# RAM.net
KiCad netlist of a schematic drawn in EasyEDA Pro
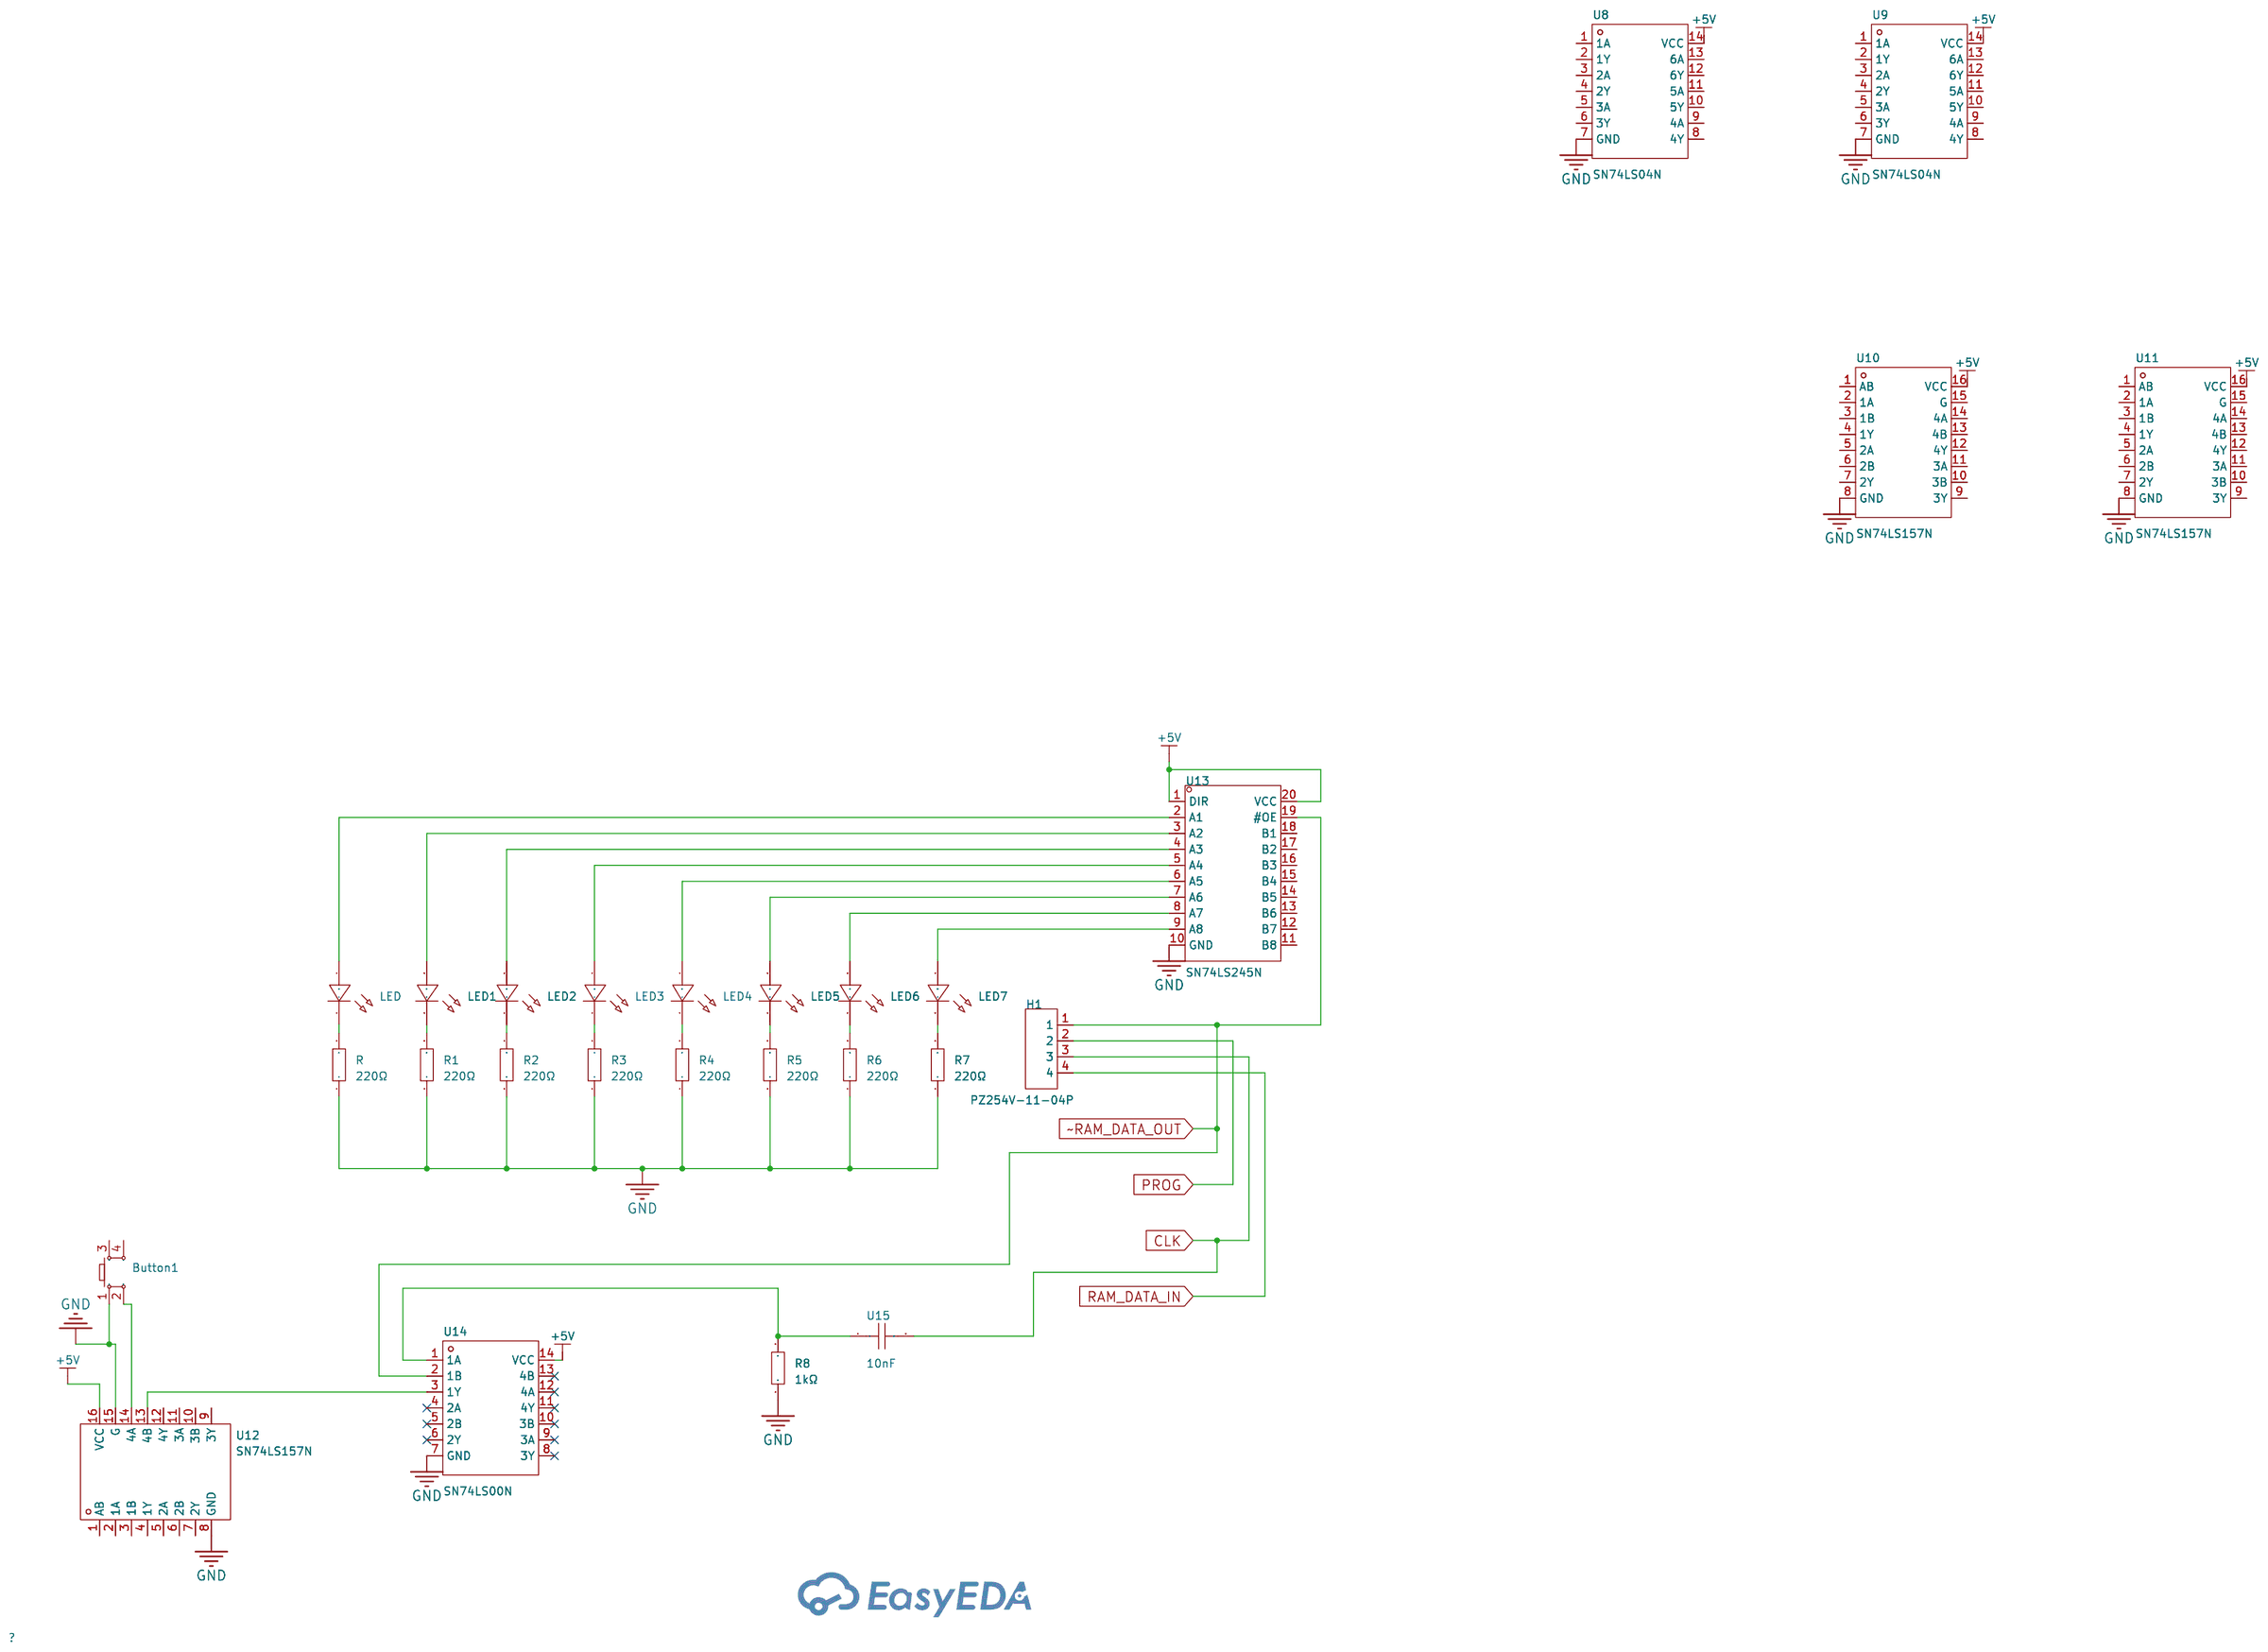
[diagram p0: schematic sheet]

(export (version "E")
  (design (tool "Eeschema 10.0.6"))
  (components
    (comp (ref "Button1")
      (value "~")
      (footprint "easyedapro:SW-TH_4P-L6.0-W6.0-P4.50-LS6.5")
      (libsource (lib "easyedapro") (part "轻触按键"))
    )
    (comp (ref "H1")
      (value "PZ254V-11-04P")
      (footprint "easyedapro:HDR-TH_4P-P2.54-V-M")
      (fields (field (name "Manufacturer") "XFCN(兴飞)"))
      (libsource (lib "easyedapro") (part "PZ254V-11-04P"))
    )
    (comp (ref "LED")
      (value "~")
      (footprint "easyedapro:LED-TH_BD5.8-P2.54-FD")
      (libsource (lib "easyedapro") (part "LED_TH-R"))
    )
    (comp (ref "LED1")
      (value "~")
      (footprint "easyedapro:LED-TH_BD5.8-P2.54-FD")
      (libsource (lib "easyedapro") (part "LED_TH-R"))
    )
    (comp (ref "LED2")
      (value "~")
      (footprint "easyedapro:LED-TH_BD5.8-P2.54-FD")
      (libsource (lib "easyedapro") (part "LED_TH-R"))
    )
    (comp (ref "LED3")
      (value "~")
      (footprint "easyedapro:LED-TH_BD5.8-P2.54-FD")
      (libsource (lib "easyedapro") (part "LED_TH-R"))
    )
    (comp (ref "LED4")
      (value "~")
      (footprint "easyedapro:LED-TH_BD5.8-P2.54-FD")
      (libsource (lib "easyedapro") (part "LED_TH-R"))
    )
    (comp (ref "LED5")
      (value "~")
      (footprint "easyedapro:LED-TH_BD5.8-P2.54-FD")
      (libsource (lib "easyedapro") (part "LED_TH-R"))
    )
    (comp (ref "LED6")
      (value "~")
      (footprint "easyedapro:LED-TH_BD5.8-P2.54-FD")
      (libsource (lib "easyedapro") (part "LED_TH-R"))
    )
    (comp (ref "LED7")
      (value "~")
      (footprint "easyedapro:LED-TH_BD5.8-P2.54-FD")
      (libsource (lib "easyedapro") (part "LED_TH-R"))
    )
    (comp (ref "R")
      (value "220Ω")
      (footprint "easyedapro:R_AXIAL-0.4")
      (libsource (lib "easyedapro") (part "Res"))
    )
    (comp (ref "R1")
      (value "220Ω")
      (footprint "easyedapro:R_AXIAL-0.4")
      (libsource (lib "easyedapro") (part "Res"))
    )
    (comp (ref "R2")
      (value "220Ω")
      (footprint "easyedapro:R_AXIAL-0.4")
      (libsource (lib "easyedapro") (part "Res"))
    )
    (comp (ref "R3")
      (value "220Ω")
      (footprint "easyedapro:R_AXIAL-0.4")
      (libsource (lib "easyedapro") (part "Res"))
    )
    (comp (ref "R4")
      (value "220Ω")
      (footprint "easyedapro:R_AXIAL-0.4")
      (libsource (lib "easyedapro") (part "Res"))
    )
    (comp (ref "R5")
      (value "220Ω")
      (footprint "easyedapro:R_AXIAL-0.4")
      (libsource (lib "easyedapro") (part "Res"))
    )
    (comp (ref "R6")
      (value "220Ω")
      (footprint "easyedapro:R_AXIAL-0.4")
      (libsource (lib "easyedapro") (part "Res"))
    )
    (comp (ref "R7")
      (value "220Ω")
      (footprint "easyedapro:R_AXIAL-0.4")
      (libsource (lib "easyedapro") (part "Res"))
    )
    (comp (ref "R8")
      (value "1kΩ")
      (footprint "easyedapro:R_AXIAL-0.4")
      (libsource (lib "easyedapro") (part "Res"))
    )
    (comp (ref "U8")
      (value "SN74LS04N")
      (footprint "easyedapro:PDIP-14_L19.7-W6.6-P2.54-LS8.3-BL")
      (fields (field (name "Manufacturer") "TI(德州仪器)"))
      (libsource (lib "easyedapro") (part "SN74LS04N"))
    )
    (comp (ref "U9")
      (value "SN74LS04N")
      (footprint "easyedapro:PDIP-14_L19.7-W6.6-P2.54-LS8.3-BL")
      (fields (field (name "Manufacturer") "TI(德州仪器)"))
      (libsource (lib "easyedapro") (part "SN74LS04N"))
    )
    (comp (ref "U10")
      (value "SN74LS157N")
      (footprint "easyedapro:DIP-16_16P-L20.2-W6.6-P2.54-LS7.6-BL")
      (fields (field (name "Manufacturer") "TI(德州仪器)"))
      (libsource (lib "easyedapro") (part "SN74LS157N"))
    )
    (comp (ref "U11")
      (value "SN74LS157N")
      (footprint "easyedapro:DIP-16_16P-L20.2-W6.6-P2.54-LS7.6-BL")
      (fields (field (name "Manufacturer") "TI(德州仪器)"))
      (libsource (lib "easyedapro") (part "SN74LS157N"))
    )
    (comp (ref "U12")
      (value "SN74LS157N")
      (footprint "easyedapro:DIP-16_16P-L20.2-W6.6-P2.54-LS7.6-BL")
      (fields (field (name "Manufacturer") "TI(德州仪器)"))
      (libsource (lib "easyedapro") (part "SN74LS157N"))
    )
    (comp (ref "U13")
      (value "SN74LS245N")
      (footprint "easyedapro:DIP-20_L25.5-W10.0-P2.54-LS7.6-BL")
      (fields (field (name "Manufacturer") "TI(德州仪器)"))
      (libsource (lib "easyedapro") (part "SN74LS245N"))
    )
    (comp (ref "U14")
      (value "SN74LS00N")
      (footprint "easyedapro:PDIP-14_L19.7-W6.6-P2.54-LS8.3-BL")
      (fields (field (name "Manufacturer") "TI(德州仪器)"))
      (libsource (lib "easyedapro") (part "SN74LS00N"))
    )
    (comp (ref "U15")
      (value "10nF")
      (footprint "easyedapro:CAP-TH_L5.8-W3.6-P5.0-D0.6")
      (description "Capacitance:10nF Tolerance:±10% Tolerance:±10% Voltage Rating:50V Temperature Coefficient:X7R")
      (fields (field (name "Manufacturer Part") "178MU0008") (field (name "Manufacturer") "KNSCHA(科尼盛)"))
      (libsource (lib "easyedapro") (part "178MU0008"))
    )
  )
  (nets
    (net (code "1") (name "+5V") (class "Default")
      (node (ref "U10") (pin "16") (pinfunction "VCC_16") (pintype "unspecified"))
      (node (ref "U11") (pin "16") (pinfunction "VCC_16") (pintype "unspecified"))
      (node (ref "U12") (pin "16") (pinfunction "VCC_16") (pintype "unspecified"))
      (node (ref "U13") (pin "1") (pinfunction "DIR_1") (pintype "input"))
      (node (ref "U13") (pin "20") (pinfunction "VCC_20") (pintype "input"))
      (node (ref "U14") (pin "14") (pinfunction "VCC_14") (pintype "unspecified"))
      (node (ref "U8") (pin "14") (pinfunction "VCC_14") (pintype "unspecified"))
      (node (ref "U9") (pin "14") (pinfunction "VCC_14") (pintype "unspecified"))
    )
    (net (code "2") (name "CLK") (class "Default")
      (node (ref "H1") (pin "3") (pinfunction "3_3") (pintype "unspecified"))
      (node (ref "U15") (pin "2") (pinfunction "2_2") (pintype "unspecified"))
    )
    (net (code "3") (name "GND") (class "Default")
      (node (ref "Button1") (pin "1") (pinfunction "1_1") (pintype "input"))
      (node (ref "R") (pin "1") (pinfunction "1_1") (pintype "input"))
      (node (ref "R1") (pin "1") (pinfunction "1_1") (pintype "input"))
      (node (ref "R2") (pin "1") (pinfunction "1_1") (pintype "input"))
      (node (ref "R3") (pin "1") (pinfunction "1_1") (pintype "input"))
      (node (ref "R4") (pin "1") (pinfunction "1_1") (pintype "input"))
      (node (ref "R5") (pin "1") (pinfunction "1_1") (pintype "input"))
      (node (ref "R6") (pin "1") (pinfunction "1_1") (pintype "input"))
      (node (ref "R7") (pin "1") (pinfunction "1_1") (pintype "input"))
      (node (ref "R8") (pin "1") (pinfunction "1_1") (pintype "input"))
      (node (ref "U10") (pin "8") (pinfunction "GND_8") (pintype "unspecified"))
      (node (ref "U11") (pin "8") (pinfunction "GND_8") (pintype "unspecified"))
      (node (ref "U12") (pin "15") (pinfunction "G_15") (pintype "unspecified"))
      (node (ref "U12") (pin "8") (pinfunction "GND_8") (pintype "unspecified"))
      (node (ref "U13") (pin "10") (pinfunction "GND_10") (pintype "input"))
      (node (ref "U14") (pin "7") (pinfunction "GND_7") (pintype "unspecified"))
      (node (ref "U8") (pin "7") (pinfunction "GND_7") (pintype "unspecified"))
      (node (ref "U9") (pin "7") (pinfunction "GND_7") (pintype "unspecified"))
    )
    (net (code "4") (name "Net-(LED-A)") (class "Default")
      (node (ref "LED") (pin "2") (pinfunction "A_2") (pintype "input"))
      (node (ref "R") (pin "2") (pinfunction "2_2") (pintype "input"))
    )
    (net (code "5") (name "Net-(LED-C)") (class "Default")
      (node (ref "LED") (pin "1") (pinfunction "C_1") (pintype "input"))
      (node (ref "U13") (pin "2") (pinfunction "A1_2") (pintype "input"))
    )
    (net (code "6") (name "Net-(LED1-A)") (class "Default")
      (node (ref "LED1") (pin "2") (pinfunction "A_2") (pintype "input"))
      (node (ref "R1") (pin "2") (pinfunction "2_2") (pintype "input"))
    )
    (net (code "7") (name "Net-(LED1-C)") (class "Default")
      (node (ref "LED1") (pin "1") (pinfunction "C_1") (pintype "input"))
      (node (ref "U13") (pin "3") (pinfunction "A2_3") (pintype "input"))
    )
    (net (code "8") (name "Net-(LED2-A)") (class "Default")
      (node (ref "LED2") (pin "2") (pinfunction "A_2") (pintype "input"))
      (node (ref "R2") (pin "2") (pinfunction "2_2") (pintype "input"))
    )
    (net (code "9") (name "Net-(LED2-C)") (class "Default")
      (node (ref "LED2") (pin "1") (pinfunction "C_1") (pintype "input"))
      (node (ref "U13") (pin "4") (pinfunction "A3_4") (pintype "input"))
    )
    (net (code "10") (name "Net-(LED3-A)") (class "Default")
      (node (ref "LED3") (pin "2") (pinfunction "A_2") (pintype "input"))
      (node (ref "R3") (pin "2") (pinfunction "2_2") (pintype "input"))
    )
    (net (code "11") (name "Net-(LED3-C)") (class "Default")
      (node (ref "LED3") (pin "1") (pinfunction "C_1") (pintype "input"))
      (node (ref "U13") (pin "5") (pinfunction "A4_5") (pintype "input"))
    )
    (net (code "12") (name "Net-(LED4-A)") (class "Default")
      (node (ref "LED4") (pin "2") (pinfunction "A_2") (pintype "input"))
      (node (ref "R4") (pin "2") (pinfunction "2_2") (pintype "input"))
    )
    (net (code "13") (name "Net-(LED4-C)") (class "Default")
      (node (ref "LED4") (pin "1") (pinfunction "C_1") (pintype "input"))
      (node (ref "U13") (pin "6") (pinfunction "A5_6") (pintype "input"))
    )
    (net (code "14") (name "Net-(LED5-A)") (class "Default")
      (node (ref "LED5") (pin "2") (pinfunction "A_2") (pintype "input"))
      (node (ref "R5") (pin "2") (pinfunction "2_2") (pintype "input"))
    )
    (net (code "15") (name "Net-(LED5-C)") (class "Default")
      (node (ref "LED5") (pin "1") (pinfunction "C_1") (pintype "input"))
      (node (ref "U13") (pin "7") (pinfunction "A6_7") (pintype "input"))
    )
    (net (code "16") (name "Net-(LED6-A)") (class "Default")
      (node (ref "LED6") (pin "2") (pinfunction "A_2") (pintype "input"))
      (node (ref "R6") (pin "2") (pinfunction "2_2") (pintype "input"))
    )
    (net (code "17") (name "Net-(LED6-C)") (class "Default")
      (node (ref "LED6") (pin "1") (pinfunction "C_1") (pintype "input"))
      (node (ref "U13") (pin "8") (pinfunction "A7_8") (pintype "input"))
    )
    (net (code "18") (name "Net-(LED7-A)") (class "Default")
      (node (ref "LED7") (pin "2") (pinfunction "A_2") (pintype "input"))
      (node (ref "R7") (pin "2") (pinfunction "2_2") (pintype "input"))
    )
    (net (code "19") (name "Net-(LED7-C)") (class "Default")
      (node (ref "LED7") (pin "1") (pinfunction "C_1") (pintype "input"))
      (node (ref "U13") (pin "9") (pinfunction "A8_9") (pintype "input"))
    )
    (net (code "20") (name "Net-(U12-4A)") (class "Default")
      (node (ref "Button1") (pin "2") (pinfunction "2_2") (pintype "input"))
      (node (ref "U12") (pin "14") (pinfunction "4A_14") (pintype "unspecified"))
    )
    (net (code "21") (name "Net-(U12-4B)") (class "Default")
      (node (ref "U12") (pin "13") (pinfunction "4B_13") (pintype "unspecified"))
      (node (ref "U14") (pin "3") (pinfunction "1Y_3") (pintype "unspecified"))
    )
    (net (code "22") (name "Net-(U14-1A)") (class "Default")
      (node (ref "R8") (pin "2") (pinfunction "2_2") (pintype "input"))
      (node (ref "U14") (pin "1") (pinfunction "1A_1") (pintype "unspecified"))
      (node (ref "U15") (pin "1") (pinfunction "1_1") (pintype "unspecified"))
    )
    (net (code "23") (name "PROG") (class "Default")
      (node (ref "H1") (pin "2") (pinfunction "2_2") (pintype "unspecified"))
    )
    (net (code "24") (name "RAM_DATA_IN") (class "Default")
      (node (ref "H1") (pin "4") (pinfunction "4_4") (pintype "unspecified"))
    )
    (net (code "25") (name "unconnected-(Button1-Pad3)") (class "Default")
      (node (ref "Button1") (pin "3") (pinfunction "3_3") (pintype "input"))
    )
    (net (code "26") (name "unconnected-(Button1-Pad4)") (class "Default")
      (node (ref "Button1") (pin "4") (pinfunction "4_4") (pintype "input"))
    )
    (net (code "27") (name "unconnected-(U8-1A-Pad1)") (class "Default")
      (node (ref "U8") (pin "1") (pinfunction "1A_1") (pintype "unspecified"))
    )
    (net (code "28") (name "unconnected-(U8-1Y-Pad2)") (class "Default")
      (node (ref "U8") (pin "2") (pinfunction "1Y_2") (pintype "unspecified"))
    )
    (net (code "29") (name "unconnected-(U8-2A-Pad3)") (class "Default")
      (node (ref "U8") (pin "3") (pinfunction "2A_3") (pintype "unspecified"))
    )
    (net (code "30") (name "unconnected-(U8-2Y-Pad4)") (class "Default")
      (node (ref "U8") (pin "4") (pinfunction "2Y_4") (pintype "unspecified"))
    )
    (net (code "31") (name "unconnected-(U8-3A-Pad5)") (class "Default")
      (node (ref "U8") (pin "5") (pinfunction "3A_5") (pintype "unspecified"))
    )
    (net (code "32") (name "unconnected-(U8-3Y-Pad6)") (class "Default")
      (node (ref "U8") (pin "6") (pinfunction "3Y_6") (pintype "unspecified"))
    )
    (net (code "33") (name "unconnected-(U8-4A-Pad9)") (class "Default")
      (node (ref "U8") (pin "9") (pinfunction "4A_9") (pintype "unspecified"))
    )
    (net (code "34") (name "unconnected-(U8-4Y-Pad8)") (class "Default")
      (node (ref "U8") (pin "8") (pinfunction "4Y_8") (pintype "unspecified"))
    )
    (net (code "35") (name "unconnected-(U8-5A-Pad11)") (class "Default")
      (node (ref "U8") (pin "11") (pinfunction "5A_11") (pintype "unspecified"))
    )
    (net (code "36") (name "unconnected-(U8-5Y-Pad10)") (class "Default")
      (node (ref "U8") (pin "10") (pinfunction "5Y_10") (pintype "unspecified"))
    )
    (net (code "37") (name "unconnected-(U8-6A-Pad13)") (class "Default")
      (node (ref "U8") (pin "13") (pinfunction "6A_13") (pintype "unspecified"))
    )
    (net (code "38") (name "unconnected-(U8-6Y-Pad12)") (class "Default")
      (node (ref "U8") (pin "12") (pinfunction "6Y_12") (pintype "unspecified"))
    )
    (net (code "39") (name "unconnected-(U9-1A-Pad1)") (class "Default")
      (node (ref "U9") (pin "1") (pinfunction "1A_1") (pintype "unspecified"))
    )
    (net (code "40") (name "unconnected-(U9-1Y-Pad2)") (class "Default")
      (node (ref "U9") (pin "2") (pinfunction "1Y_2") (pintype "unspecified"))
    )
    (net (code "41") (name "unconnected-(U9-2A-Pad3)") (class "Default")
      (node (ref "U9") (pin "3") (pinfunction "2A_3") (pintype "unspecified"))
    )
    (net (code "42") (name "unconnected-(U9-2Y-Pad4)") (class "Default")
      (node (ref "U9") (pin "4") (pinfunction "2Y_4") (pintype "unspecified"))
    )
    (net (code "43") (name "unconnected-(U9-3A-Pad5)") (class "Default")
      (node (ref "U9") (pin "5") (pinfunction "3A_5") (pintype "unspecified"))
    )
    (net (code "44") (name "unconnected-(U9-3Y-Pad6)") (class "Default")
      (node (ref "U9") (pin "6") (pinfunction "3Y_6") (pintype "unspecified"))
    )
    (net (code "45") (name "unconnected-(U9-4A-Pad9)") (class "Default")
      (node (ref "U9") (pin "9") (pinfunction "4A_9") (pintype "unspecified"))
    )
    (net (code "46") (name "unconnected-(U9-4Y-Pad8)") (class "Default")
      (node (ref "U9") (pin "8") (pinfunction "4Y_8") (pintype "unspecified"))
    )
    (net (code "47") (name "unconnected-(U9-5A-Pad11)") (class "Default")
      (node (ref "U9") (pin "11") (pinfunction "5A_11") (pintype "unspecified"))
    )
    (net (code "48") (name "unconnected-(U9-5Y-Pad10)") (class "Default")
      (node (ref "U9") (pin "10") (pinfunction "5Y_10") (pintype "unspecified"))
    )
    (net (code "49") (name "unconnected-(U9-6A-Pad13)") (class "Default")
      (node (ref "U9") (pin "13") (pinfunction "6A_13") (pintype "unspecified"))
    )
    (net (code "50") (name "unconnected-(U9-6Y-Pad12)") (class "Default")
      (node (ref "U9") (pin "12") (pinfunction "6Y_12") (pintype "unspecified"))
    )
    (net (code "51") (name "unconnected-(U10-1A-Pad2)") (class "Default")
      (node (ref "U10") (pin "2") (pinfunction "1A_2") (pintype "unspecified"))
    )
    (net (code "52") (name "unconnected-(U10-1B-Pad3)") (class "Default")
      (node (ref "U10") (pin "3") (pinfunction "1B_3") (pintype "unspecified"))
    )
    (net (code "53") (name "unconnected-(U10-1Y-Pad4)") (class "Default")
      (node (ref "U10") (pin "4") (pinfunction "1Y_4") (pintype "unspecified"))
    )
    (net (code "54") (name "unconnected-(U10-2A-Pad5)") (class "Default")
      (node (ref "U10") (pin "5") (pinfunction "2A_5") (pintype "unspecified"))
    )
    (net (code "55") (name "unconnected-(U10-2B-Pad6)") (class "Default")
      (node (ref "U10") (pin "6") (pinfunction "2B_6") (pintype "unspecified"))
    )
    (net (code "56") (name "unconnected-(U10-2Y-Pad7)") (class "Default")
      (node (ref "U10") (pin "7") (pinfunction "2Y_7") (pintype "unspecified"))
    )
    (net (code "57") (name "unconnected-(U10-3A-Pad11)") (class "Default")
      (node (ref "U10") (pin "11") (pinfunction "3A_11") (pintype "unspecified"))
    )
    (net (code "58") (name "unconnected-(U10-3B-Pad10)") (class "Default")
      (node (ref "U10") (pin "10") (pinfunction "3B_10") (pintype "unspecified"))
    )
    (net (code "59") (name "unconnected-(U10-3Y-Pad9)") (class "Default")
      (node (ref "U10") (pin "9") (pinfunction "3Y_9") (pintype "unspecified"))
    )
    (net (code "60") (name "unconnected-(U10-4A-Pad14)") (class "Default")
      (node (ref "U10") (pin "14") (pinfunction "4A_14") (pintype "unspecified"))
    )
    (net (code "61") (name "unconnected-(U10-4B-Pad13)") (class "Default")
      (node (ref "U10") (pin "13") (pinfunction "4B_13") (pintype "unspecified"))
    )
    (net (code "62") (name "unconnected-(U10-4Y-Pad12)") (class "Default")
      (node (ref "U10") (pin "12") (pinfunction "4Y_12") (pintype "unspecified"))
    )
    (net (code "63") (name "unconnected-(U10-AB-Pad1)") (class "Default")
      (node (ref "U10") (pin "1") (pinfunction "AB_1") (pintype "unspecified"))
    )
    (net (code "64") (name "unconnected-(U10-G-Pad15)") (class "Default")
      (node (ref "U10") (pin "15") (pinfunction "G_15") (pintype "unspecified"))
    )
    (net (code "65") (name "unconnected-(U11-1A-Pad2)") (class "Default")
      (node (ref "U11") (pin "2") (pinfunction "1A_2") (pintype "unspecified"))
    )
    (net (code "66") (name "unconnected-(U11-1B-Pad3)") (class "Default")
      (node (ref "U11") (pin "3") (pinfunction "1B_3") (pintype "unspecified"))
    )
    (net (code "67") (name "unconnected-(U11-1Y-Pad4)") (class "Default")
      (node (ref "U11") (pin "4") (pinfunction "1Y_4") (pintype "unspecified"))
    )
    (net (code "68") (name "unconnected-(U11-2A-Pad5)") (class "Default")
      (node (ref "U11") (pin "5") (pinfunction "2A_5") (pintype "unspecified"))
    )
    (net (code "69") (name "unconnected-(U11-2B-Pad6)") (class "Default")
      (node (ref "U11") (pin "6") (pinfunction "2B_6") (pintype "unspecified"))
    )
    (net (code "70") (name "unconnected-(U11-2Y-Pad7)") (class "Default")
      (node (ref "U11") (pin "7") (pinfunction "2Y_7") (pintype "unspecified"))
    )
    (net (code "71") (name "unconnected-(U11-3A-Pad11)") (class "Default")
      (node (ref "U11") (pin "11") (pinfunction "3A_11") (pintype "unspecified"))
    )
    (net (code "72") (name "unconnected-(U11-3B-Pad10)") (class "Default")
      (node (ref "U11") (pin "10") (pinfunction "3B_10") (pintype "unspecified"))
    )
    (net (code "73") (name "unconnected-(U11-3Y-Pad9)") (class "Default")
      (node (ref "U11") (pin "9") (pinfunction "3Y_9") (pintype "unspecified"))
    )
    (net (code "74") (name "unconnected-(U11-4A-Pad14)") (class "Default")
      (node (ref "U11") (pin "14") (pinfunction "4A_14") (pintype "unspecified"))
    )
    (net (code "75") (name "unconnected-(U11-4B-Pad13)") (class "Default")
      (node (ref "U11") (pin "13") (pinfunction "4B_13") (pintype "unspecified"))
    )
    (net (code "76") (name "unconnected-(U11-4Y-Pad12)") (class "Default")
      (node (ref "U11") (pin "12") (pinfunction "4Y_12") (pintype "unspecified"))
    )
    (net (code "77") (name "unconnected-(U11-AB-Pad1)") (class "Default")
      (node (ref "U11") (pin "1") (pinfunction "AB_1") (pintype "unspecified"))
    )
    (net (code "78") (name "unconnected-(U11-G-Pad15)") (class "Default")
      (node (ref "U11") (pin "15") (pinfunction "G_15") (pintype "unspecified"))
    )
    (net (code "79") (name "unconnected-(U12-1A-Pad2)") (class "Default")
      (node (ref "U12") (pin "2") (pinfunction "1A_2") (pintype "unspecified"))
    )
    (net (code "80") (name "unconnected-(U12-1B-Pad3)") (class "Default")
      (node (ref "U12") (pin "3") (pinfunction "1B_3") (pintype "unspecified"))
    )
    (net (code "81") (name "unconnected-(U12-1Y-Pad4)") (class "Default")
      (node (ref "U12") (pin "4") (pinfunction "1Y_4") (pintype "unspecified"))
    )
    (net (code "82") (name "unconnected-(U12-2A-Pad5)") (class "Default")
      (node (ref "U12") (pin "5") (pinfunction "2A_5") (pintype "unspecified"))
    )
    (net (code "83") (name "unconnected-(U12-2B-Pad6)") (class "Default")
      (node (ref "U12") (pin "6") (pinfunction "2B_6") (pintype "unspecified"))
    )
    (net (code "84") (name "unconnected-(U12-2Y-Pad7)") (class "Default")
      (node (ref "U12") (pin "7") (pinfunction "2Y_7") (pintype "unspecified"))
    )
    (net (code "85") (name "unconnected-(U12-3A-Pad11)") (class "Default")
      (node (ref "U12") (pin "11") (pinfunction "3A_11") (pintype "unspecified"))
    )
    (net (code "86") (name "unconnected-(U12-3B-Pad10)") (class "Default")
      (node (ref "U12") (pin "10") (pinfunction "3B_10") (pintype "unspecified"))
    )
    (net (code "87") (name "unconnected-(U12-3Y-Pad9)") (class "Default")
      (node (ref "U12") (pin "9") (pinfunction "3Y_9") (pintype "unspecified"))
    )
    (net (code "88") (name "unconnected-(U12-4Y-Pad12)") (class "Default")
      (node (ref "U12") (pin "12") (pinfunction "4Y_12") (pintype "unspecified"))
    )
    (net (code "89") (name "unconnected-(U12-AB-Pad1)") (class "Default")
      (node (ref "U12") (pin "1") (pinfunction "AB_1") (pintype "unspecified"))
    )
    (net (code "90") (name "unconnected-(U13-B1-Pad18)") (class "Default")
      (node (ref "U13") (pin "18") (pinfunction "B1_18") (pintype "input"))
    )
    (net (code "91") (name "unconnected-(U13-B2-Pad17)") (class "Default")
      (node (ref "U13") (pin "17") (pinfunction "B2_17") (pintype "input"))
    )
    (net (code "92") (name "unconnected-(U13-B3-Pad16)") (class "Default")
      (node (ref "U13") (pin "16") (pinfunction "B3_16") (pintype "input"))
    )
    (net (code "93") (name "unconnected-(U13-B4-Pad15)") (class "Default")
      (node (ref "U13") (pin "15") (pinfunction "B4_15") (pintype "input"))
    )
    (net (code "94") (name "unconnected-(U13-B5-Pad14)") (class "Default")
      (node (ref "U13") (pin "14") (pinfunction "B5_14") (pintype "input"))
    )
    (net (code "95") (name "unconnected-(U13-B6-Pad13)") (class "Default")
      (node (ref "U13") (pin "13") (pinfunction "B6_13") (pintype "input"))
    )
    (net (code "96") (name "unconnected-(U13-B7-Pad12)") (class "Default")
      (node (ref "U13") (pin "12") (pinfunction "B7_12") (pintype "input"))
    )
    (net (code "97") (name "unconnected-(U13-B8-Pad11)") (class "Default")
      (node (ref "U13") (pin "11") (pinfunction "B8_11") (pintype "input"))
    )
    (net (code "98") (name "unconnected-(U14-2A-Pad4)") (class "Default")
      (node (ref "U14") (pin "4") (pinfunction "2A_4") (pintype "unspecified+no_connect"))
    )
    (net (code "99") (name "unconnected-(U14-2B-Pad5)") (class "Default")
      (node (ref "U14") (pin "5") (pinfunction "2B_5") (pintype "unspecified+no_connect"))
    )
    (net (code "100") (name "unconnected-(U14-2Y-Pad6)") (class "Default")
      (node (ref "U14") (pin "6") (pinfunction "2Y_6") (pintype "unspecified+no_connect"))
    )
    (net (code "101") (name "unconnected-(U14-3A-Pad9)") (class "Default")
      (node (ref "U14") (pin "9") (pinfunction "3A_9") (pintype "unspecified+no_connect"))
    )
    (net (code "102") (name "unconnected-(U14-3B-Pad10)") (class "Default")
      (node (ref "U14") (pin "10") (pinfunction "3B_10") (pintype "unspecified+no_connect"))
    )
    (net (code "103") (name "unconnected-(U14-3Y-Pad8)") (class "Default")
      (node (ref "U14") (pin "8") (pinfunction "3Y_8") (pintype "unspecified+no_connect"))
    )
    (net (code "104") (name "unconnected-(U14-4A-Pad12)") (class "Default")
      (node (ref "U14") (pin "12") (pinfunction "4A_12") (pintype "unspecified+no_connect"))
    )
    (net (code "105") (name "unconnected-(U14-4B-Pad13)") (class "Default")
      (node (ref "U14") (pin "13") (pinfunction "4B_13") (pintype "unspecified+no_connect"))
    )
    (net (code "106") (name "unconnected-(U14-4Y-Pad11)") (class "Default")
      (node (ref "U14") (pin "11") (pinfunction "4Y_11") (pintype "unspecified+no_connect"))
    )
    (net (code "107") (name "~RAM_DATA_OUT") (class "Default")
      (node (ref "H1") (pin "1") (pinfunction "1_1") (pintype "unspecified"))
      (node (ref "U13") (pin "19") (pinfunction "#OE_19") (pintype "input"))
      (node (ref "U14") (pin "2") (pinfunction "1B_2") (pintype "unspecified"))
    )
  )
)
